# ADC_Board_Two_Board.net
KiCad netlist of a schematic drawn in EAGLE
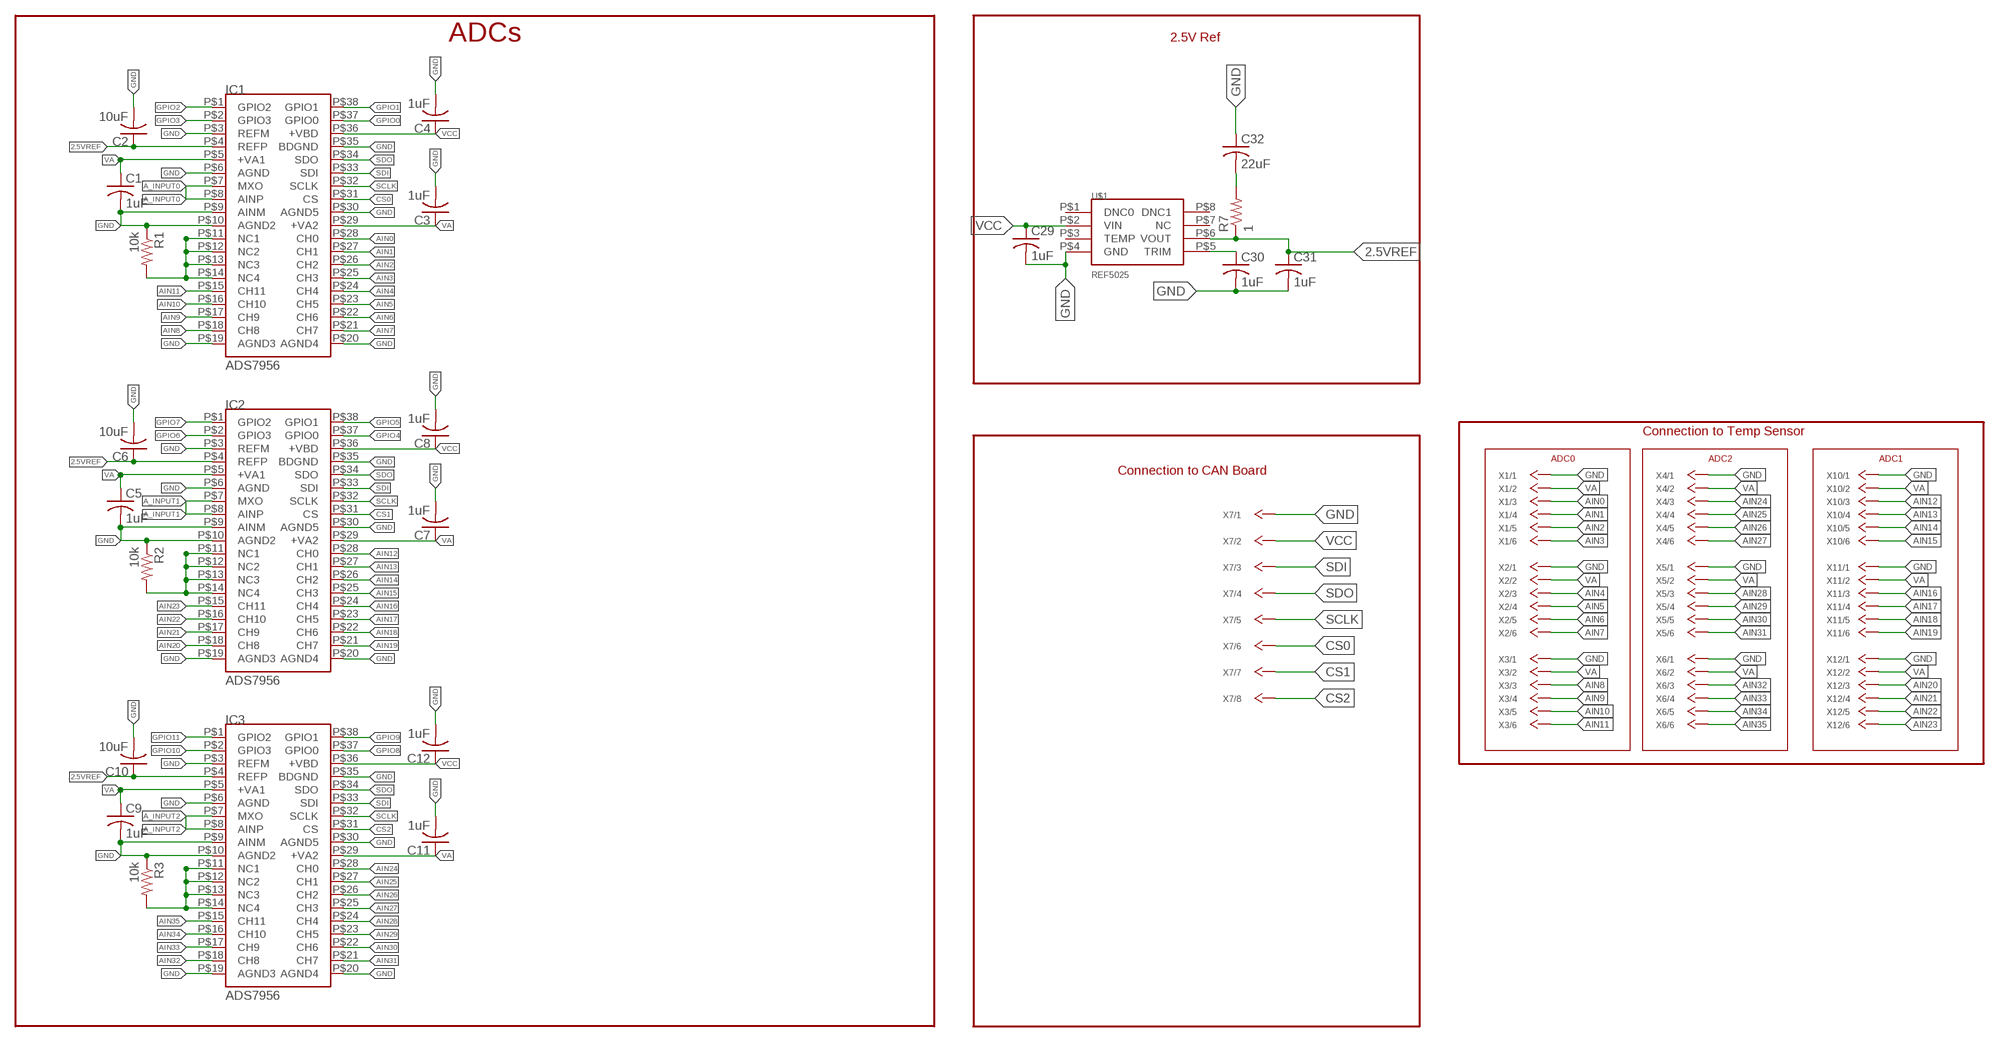
[diagram p0: schematic, sheet 1]

(export (version "E")
  (design (tool "Eeschema 10.0.6"))
  (components
    (comp (ref "C1")
      (value "1uF")
      (footprint "eagle-import:C0603")
      (libsource (lib "eagle-import") (part "C-USC0603"))
    )
    (comp (ref "C2")
      (value "10uF")
      (footprint "eagle-import:C0603")
      (libsource (lib "eagle-import") (part "C-USC0603"))
    )
    (comp (ref "C3")
      (value "1uF")
      (footprint "eagle-import:C0603")
      (libsource (lib "eagle-import") (part "C-USC0603"))
    )
    (comp (ref "C4")
      (value "1uF")
      (footprint "eagle-import:C0603")
      (libsource (lib "eagle-import") (part "C-USC0603"))
    )
    (comp (ref "C5")
      (value "1uF")
      (footprint "eagle-import:C0603")
      (libsource (lib "eagle-import") (part "C-USC0603"))
    )
    (comp (ref "C6")
      (value "10uF")
      (footprint "eagle-import:C0603")
      (libsource (lib "eagle-import") (part "C-USC0603"))
    )
    (comp (ref "C7")
      (value "1uF")
      (footprint "eagle-import:C0603")
      (libsource (lib "eagle-import") (part "C-USC0603"))
    )
    (comp (ref "C8")
      (value "1uF")
      (footprint "eagle-import:C0603")
      (libsource (lib "eagle-import") (part "C-USC0603"))
    )
    (comp (ref "C9")
      (value "1uF")
      (footprint "eagle-import:C0603")
      (libsource (lib "eagle-import") (part "C-USC0603"))
    )
    (comp (ref "C10")
      (value "10uF")
      (footprint "eagle-import:C0603")
      (libsource (lib "eagle-import") (part "C-USC0603"))
    )
    (comp (ref "C11")
      (value "1uF")
      (footprint "eagle-import:C0603")
      (libsource (lib "eagle-import") (part "C-USC0603"))
    )
    (comp (ref "C12")
      (value "1uF")
      (footprint "eagle-import:C0603")
      (libsource (lib "eagle-import") (part "C-USC0603"))
    )
    (comp (ref "C29")
      (value "1uF")
      (footprint "eagle-import:C0603")
      (libsource (lib "eagle-import") (part "C-USC0603"))
    )
    (comp (ref "C30")
      (value "1uF")
      (footprint "eagle-import:C0603")
      (libsource (lib "eagle-import") (part "C-USC0603"))
    )
    (comp (ref "C31")
      (value "1uF")
      (footprint "eagle-import:C0603")
      (libsource (lib "eagle-import") (part "C-USC0603"))
    )
    (comp (ref "C32")
      (value "22uF")
      (footprint "eagle-import:C0603")
      (libsource (lib "eagle-import") (part "C-USC0603"))
    )
    (comp (ref "IC1")
      (value "ADS7956")
      (footprint "eagle-import:TSSOP-38")
      (libsource (lib "eagle-import") (part "ADS7956"))
    )
    (comp (ref "IC2")
      (value "ADS7956")
      (footprint "eagle-import:TSSOP-38")
      (libsource (lib "eagle-import") (part "ADS7956"))
    )
    (comp (ref "IC3")
      (value "ADS7956")
      (footprint "eagle-import:TSSOP-38")
      (libsource (lib "eagle-import") (part "ADS7956"))
    )
    (comp (ref "R1")
      (value "10k")
      (footprint "eagle-import:R0603")
      (libsource (lib "eagle-import") (part "resistor_R-US_R0603"))
    )
    (comp (ref "R2")
      (value "10k")
      (footprint "eagle-import:R0603")
      (libsource (lib "eagle-import") (part "resistor_R-US_R0603"))
    )
    (comp (ref "R3")
      (value "10k")
      (footprint "eagle-import:R0603")
      (libsource (lib "eagle-import") (part "resistor_R-US_R0603"))
    )
    (comp (ref "R7")
      (value "1")
      (footprint "eagle-import:M0805")
      (libsource (lib "eagle-import") (part "R-US_M0805"))
    )
    (comp (ref "U$1")
      (value "REF5025")
      (footprint "eagle-import:TSSOP-8(TI)")
      (libsource (lib "eagle-import") (part "REF5025"))
    )
    (comp (ref "X1")
      (value "6_PIN_CONNTE_IDC")
      (footprint "eagle-import:2178710_IDC")
      (libsource (lib "eagle-import") (part "6_PIN_CONNTE_IDC"))
    )
    (comp (ref "X2")
      (value "6_PIN_CONNTE_IDC")
      (footprint "eagle-import:2178710_IDC")
      (libsource (lib "eagle-import") (part "6_PIN_CONNTE_IDC"))
    )
    (comp (ref "X3")
      (value "6_PIN_CONNTE_IDC")
      (footprint "eagle-import:2178710_IDC")
      (libsource (lib "eagle-import") (part "6_PIN_CONNTE_IDC"))
    )
    (comp (ref "X4")
      (value "6_PIN_CONNTE_IDC")
      (footprint "eagle-import:2178710_IDC")
      (libsource (lib "eagle-import") (part "6_PIN_CONNTE_IDC"))
    )
    (comp (ref "X5")
      (value "6_PIN_CONNTE_IDC")
      (footprint "eagle-import:2178710_IDC")
      (libsource (lib "eagle-import") (part "6_PIN_CONNTE_IDC"))
    )
    (comp (ref "X6")
      (value "6_PIN_CONNTE_IDC")
      (footprint "eagle-import:2178710_IDC")
      (libsource (lib "eagle-import") (part "6_PIN_CONNTE_IDC"))
    )
    (comp (ref "X7")
      (value "8_PIN_CONN")
      (footprint "eagle-import:8_PIN_MOLEX")
      (libsource (lib "eagle-import") (part "8_PIN_CONN"))
    )
    (comp (ref "X10")
      (value "6_PIN_CONNTE_IDC")
      (footprint "eagle-import:2178710_IDC")
      (libsource (lib "eagle-import") (part "6_PIN_CONNTE_IDC"))
    )
    (comp (ref "X11")
      (value "6_PIN_CONNTE_IDC")
      (footprint "eagle-import:2178710_IDC")
      (libsource (lib "eagle-import") (part "6_PIN_CONNTE_IDC"))
    )
    (comp (ref "X12")
      (value "6_PIN_CONNTE_IDC")
      (footprint "eagle-import:2178710_IDC")
      (libsource (lib "eagle-import") (part "6_PIN_CONNTE_IDC"))
    )
  )
  (nets
    (net (code "1") (name "2.5VREF") (class "Default")
      (node (ref "C10") (pin "1") (pinfunction "1_1") (pintype "passive"))
      (node (ref "C2") (pin "1") (pinfunction "1_1") (pintype "passive"))
      (node (ref "C31") (pin "1") (pinfunction "1_1") (pintype "passive"))
      (node (ref "C6") (pin "1") (pinfunction "1_1") (pintype "passive"))
      (node (ref "IC1") (pin "P$4") (pinfunction "REFP_P$4") (pintype "bidirectional"))
      (node (ref "IC2") (pin "P$4") (pinfunction "REFP_P$4") (pintype "bidirectional"))
      (node (ref "IC3") (pin "P$4") (pinfunction "REFP_P$4") (pintype "bidirectional"))
      (node (ref "R7") (pin "1") (pinfunction "1_1") (pintype "passive"))
      (node (ref "U$1") (pin "P$6") (pinfunction "VOUT_P$6") (pintype "bidirectional"))
    )
    (net (code "2") (name "AIN0") (class "Default")
      (node (ref "IC1") (pin "P$28") (pinfunction "CH0_P$28") (pintype "bidirectional"))
      (node (ref "X1") (pin "P$3") (pinfunction "$/1_P$3") (pintype "bidirectional"))
    )
    (net (code "3") (name "AIN1") (class "Default")
      (node (ref "IC1") (pin "P$27") (pinfunction "CH1_P$27") (pintype "bidirectional"))
      (node (ref "X1") (pin "P$4") (pinfunction "$/1_P$4") (pintype "bidirectional"))
    )
    (net (code "4") (name "AIN2") (class "Default")
      (node (ref "IC1") (pin "P$26") (pinfunction "CH2_P$26") (pintype "bidirectional"))
      (node (ref "X1") (pin "P$5") (pinfunction "$/1_P$5") (pintype "bidirectional"))
    )
    (net (code "5") (name "AIN3") (class "Default")
      (node (ref "IC1") (pin "P$25") (pinfunction "CH3_P$25") (pintype "bidirectional"))
      (node (ref "X1") (pin "P$6") (pinfunction "$/1_P$6") (pintype "bidirectional"))
    )
    (net (code "6") (name "AIN4") (class "Default")
      (node (ref "IC1") (pin "P$24") (pinfunction "CH4_P$24") (pintype "bidirectional"))
      (node (ref "X2") (pin "P$3") (pinfunction "$/1_P$3") (pintype "bidirectional"))
    )
    (net (code "7") (name "AIN5") (class "Default")
      (node (ref "IC1") (pin "P$23") (pinfunction "CH5_P$23") (pintype "bidirectional"))
      (node (ref "X2") (pin "P$4") (pinfunction "$/1_P$4") (pintype "bidirectional"))
    )
    (net (code "8") (name "AIN6") (class "Default")
      (node (ref "IC1") (pin "P$22") (pinfunction "CH6_P$22") (pintype "bidirectional"))
      (node (ref "X2") (pin "P$5") (pinfunction "$/1_P$5") (pintype "bidirectional"))
    )
    (net (code "9") (name "AIN7") (class "Default")
      (node (ref "IC1") (pin "P$21") (pinfunction "CH7_P$21") (pintype "bidirectional"))
      (node (ref "X2") (pin "P$6") (pinfunction "$/1_P$6") (pintype "bidirectional"))
    )
    (net (code "10") (name "AIN8") (class "Default")
      (node (ref "IC1") (pin "P$18") (pinfunction "CH8_P$18") (pintype "bidirectional"))
      (node (ref "X3") (pin "P$3") (pinfunction "$/1_P$3") (pintype "bidirectional"))
    )
    (net (code "11") (name "AIN9") (class "Default")
      (node (ref "IC1") (pin "P$17") (pinfunction "CH9_P$17") (pintype "bidirectional"))
      (node (ref "X3") (pin "P$4") (pinfunction "$/1_P$4") (pintype "bidirectional"))
    )
    (net (code "12") (name "AIN10") (class "Default")
      (node (ref "IC1") (pin "P$16") (pinfunction "CH10_P$16") (pintype "bidirectional"))
      (node (ref "X3") (pin "P$5") (pinfunction "$/1_P$5") (pintype "bidirectional"))
    )
    (net (code "13") (name "AIN11") (class "Default")
      (node (ref "IC1") (pin "P$15") (pinfunction "CH11_P$15") (pintype "bidirectional"))
      (node (ref "X3") (pin "P$6") (pinfunction "$/1_P$6") (pintype "bidirectional"))
    )
    (net (code "14") (name "AIN12") (class "Default")
      (node (ref "IC2") (pin "P$28") (pinfunction "CH0_P$28") (pintype "bidirectional"))
      (node (ref "X10") (pin "P$3") (pinfunction "$/1_P$3") (pintype "bidirectional"))
    )
    (net (code "15") (name "AIN13") (class "Default")
      (node (ref "IC2") (pin "P$27") (pinfunction "CH1_P$27") (pintype "bidirectional"))
      (node (ref "X10") (pin "P$4") (pinfunction "$/1_P$4") (pintype "bidirectional"))
    )
    (net (code "16") (name "AIN14") (class "Default")
      (node (ref "IC2") (pin "P$26") (pinfunction "CH2_P$26") (pintype "bidirectional"))
      (node (ref "X10") (pin "P$5") (pinfunction "$/1_P$5") (pintype "bidirectional"))
    )
    (net (code "17") (name "AIN15") (class "Default")
      (node (ref "IC2") (pin "P$25") (pinfunction "CH3_P$25") (pintype "bidirectional"))
      (node (ref "X10") (pin "P$6") (pinfunction "$/1_P$6") (pintype "bidirectional"))
    )
    (net (code "18") (name "AIN16") (class "Default")
      (node (ref "IC2") (pin "P$24") (pinfunction "CH4_P$24") (pintype "bidirectional"))
      (node (ref "X11") (pin "P$3") (pinfunction "$/1_P$3") (pintype "bidirectional"))
    )
    (net (code "19") (name "AIN17") (class "Default")
      (node (ref "IC2") (pin "P$23") (pinfunction "CH5_P$23") (pintype "bidirectional"))
      (node (ref "X11") (pin "P$4") (pinfunction "$/1_P$4") (pintype "bidirectional"))
    )
    (net (code "20") (name "AIN18") (class "Default")
      (node (ref "IC2") (pin "P$22") (pinfunction "CH6_P$22") (pintype "bidirectional"))
      (node (ref "X11") (pin "P$5") (pinfunction "$/1_P$5") (pintype "bidirectional"))
    )
    (net (code "21") (name "AIN19") (class "Default")
      (node (ref "IC2") (pin "P$21") (pinfunction "CH7_P$21") (pintype "bidirectional"))
      (node (ref "X11") (pin "P$6") (pinfunction "$/1_P$6") (pintype "bidirectional"))
    )
    (net (code "22") (name "AIN20") (class "Default")
      (node (ref "IC2") (pin "P$18") (pinfunction "CH8_P$18") (pintype "bidirectional"))
      (node (ref "X12") (pin "P$3") (pinfunction "$/1_P$3") (pintype "bidirectional"))
    )
    (net (code "23") (name "AIN21") (class "Default")
      (node (ref "IC2") (pin "P$17") (pinfunction "CH9_P$17") (pintype "bidirectional"))
      (node (ref "X12") (pin "P$4") (pinfunction "$/1_P$4") (pintype "bidirectional"))
    )
    (net (code "24") (name "AIN22") (class "Default")
      (node (ref "IC2") (pin "P$16") (pinfunction "CH10_P$16") (pintype "bidirectional"))
      (node (ref "X12") (pin "P$5") (pinfunction "$/1_P$5") (pintype "bidirectional"))
    )
    (net (code "25") (name "AIN23") (class "Default")
      (node (ref "IC2") (pin "P$15") (pinfunction "CH11_P$15") (pintype "bidirectional"))
      (node (ref "X12") (pin "P$6") (pinfunction "$/1_P$6") (pintype "bidirectional"))
    )
    (net (code "26") (name "AIN24") (class "Default")
      (node (ref "IC3") (pin "P$28") (pinfunction "CH0_P$28") (pintype "bidirectional"))
      (node (ref "X4") (pin "P$3") (pinfunction "$/1_P$3") (pintype "bidirectional"))
    )
    (net (code "27") (name "AIN25") (class "Default")
      (node (ref "IC3") (pin "P$27") (pinfunction "CH1_P$27") (pintype "bidirectional"))
      (node (ref "X4") (pin "P$4") (pinfunction "$/1_P$4") (pintype "bidirectional"))
    )
    (net (code "28") (name "AIN26") (class "Default")
      (node (ref "IC3") (pin "P$26") (pinfunction "CH2_P$26") (pintype "bidirectional"))
      (node (ref "X4") (pin "P$5") (pinfunction "$/1_P$5") (pintype "bidirectional"))
    )
    (net (code "29") (name "AIN27") (class "Default")
      (node (ref "IC3") (pin "P$25") (pinfunction "CH3_P$25") (pintype "bidirectional"))
      (node (ref "X4") (pin "P$6") (pinfunction "$/1_P$6") (pintype "bidirectional"))
    )
    (net (code "30") (name "AIN28") (class "Default")
      (node (ref "IC3") (pin "P$24") (pinfunction "CH4_P$24") (pintype "bidirectional"))
      (node (ref "X5") (pin "P$3") (pinfunction "$/1_P$3") (pintype "bidirectional"))
    )
    (net (code "31") (name "AIN29") (class "Default")
      (node (ref "IC3") (pin "P$23") (pinfunction "CH5_P$23") (pintype "bidirectional"))
      (node (ref "X5") (pin "P$4") (pinfunction "$/1_P$4") (pintype "bidirectional"))
    )
    (net (code "32") (name "AIN30") (class "Default")
      (node (ref "IC3") (pin "P$22") (pinfunction "CH6_P$22") (pintype "bidirectional"))
      (node (ref "X5") (pin "P$5") (pinfunction "$/1_P$5") (pintype "bidirectional"))
    )
    (net (code "33") (name "AIN31") (class "Default")
      (node (ref "IC3") (pin "P$21") (pinfunction "CH7_P$21") (pintype "bidirectional"))
      (node (ref "X5") (pin "P$6") (pinfunction "$/1_P$6") (pintype "bidirectional"))
    )
    (net (code "34") (name "AIN32") (class "Default")
      (node (ref "IC3") (pin "P$18") (pinfunction "CH8_P$18") (pintype "bidirectional"))
      (node (ref "X6") (pin "P$3") (pinfunction "$/1_P$3") (pintype "bidirectional"))
    )
    (net (code "35") (name "AIN33") (class "Default")
      (node (ref "IC3") (pin "P$17") (pinfunction "CH9_P$17") (pintype "bidirectional"))
      (node (ref "X6") (pin "P$4") (pinfunction "$/1_P$4") (pintype "bidirectional"))
    )
    (net (code "36") (name "AIN34") (class "Default")
      (node (ref "IC3") (pin "P$16") (pinfunction "CH10_P$16") (pintype "bidirectional"))
      (node (ref "X6") (pin "P$5") (pinfunction "$/1_P$5") (pintype "bidirectional"))
    )
    (net (code "37") (name "AIN35") (class "Default")
      (node (ref "IC3") (pin "P$15") (pinfunction "CH11_P$15") (pintype "bidirectional"))
      (node (ref "X6") (pin "P$6") (pinfunction "$/1_P$6") (pintype "bidirectional"))
    )
    (net (code "38") (name "A_INPUT0") (class "Default")
      (node (ref "IC1") (pin "P$7") (pinfunction "MXO_P$7") (pintype "bidirectional"))
      (node (ref "IC1") (pin "P$8") (pinfunction "AINP_P$8") (pintype "bidirectional"))
    )
    (net (code "39") (name "A_INPUT1") (class "Default")
      (node (ref "IC2") (pin "P$7") (pinfunction "MXO_P$7") (pintype "bidirectional"))
      (node (ref "IC2") (pin "P$8") (pinfunction "AINP_P$8") (pintype "bidirectional"))
    )
    (net (code "40") (name "A_INPUT2") (class "Default")
      (node (ref "IC3") (pin "P$7") (pinfunction "MXO_P$7") (pintype "bidirectional"))
      (node (ref "IC3") (pin "P$8") (pinfunction "AINP_P$8") (pintype "bidirectional"))
    )
    (net (code "41") (name "CS0") (class "Default")
      (node (ref "IC1") (pin "P$31") (pinfunction "CS_P$31") (pintype "bidirectional"))
      (node (ref "X7") (pin "P$6") (pinfunction "$/1_P$6") (pintype "bidirectional"))
    )
    (net (code "42") (name "CS1") (class "Default")
      (node (ref "IC2") (pin "P$31") (pinfunction "CS_P$31") (pintype "bidirectional"))
      (node (ref "X7") (pin "P$7") (pinfunction "$/1_P$7") (pintype "bidirectional"))
    )
    (net (code "43") (name "CS2") (class "Default")
      (node (ref "IC3") (pin "P$31") (pinfunction "CS_P$31") (pintype "bidirectional"))
      (node (ref "X7") (pin "P$8") (pinfunction "$/1_P$8") (pintype "bidirectional"))
    )
    (net (code "44") (name "GND") (class "Default")
      (node (ref "C1") (pin "2") (pinfunction "2_2") (pintype "passive"))
      (node (ref "C10") (pin "2") (pinfunction "2_2") (pintype "passive"))
      (node (ref "C11") (pin "2") (pinfunction "2_2") (pintype "passive"))
      (node (ref "C12") (pin "2") (pinfunction "2_2") (pintype "passive"))
      (node (ref "C2") (pin "2") (pinfunction "2_2") (pintype "passive"))
      (node (ref "C29") (pin "2") (pinfunction "2_2") (pintype "passive"))
      (node (ref "C3") (pin "2") (pinfunction "2_2") (pintype "passive"))
      (node (ref "C30") (pin "2") (pinfunction "2_2") (pintype "passive"))
      (node (ref "C31") (pin "2") (pinfunction "2_2") (pintype "passive"))
      (node (ref "C32") (pin "1") (pinfunction "1_1") (pintype "passive"))
      (node (ref "C4") (pin "2") (pinfunction "2_2") (pintype "passive"))
      (node (ref "C5") (pin "2") (pinfunction "2_2") (pintype "passive"))
      (node (ref "C6") (pin "2") (pinfunction "2_2") (pintype "passive"))
      (node (ref "C7") (pin "2") (pinfunction "2_2") (pintype "passive"))
      (node (ref "C8") (pin "2") (pinfunction "2_2") (pintype "passive"))
      (node (ref "C9") (pin "2") (pinfunction "2_2") (pintype "passive"))
      (node (ref "IC1") (pin "P$10") (pinfunction "AGND2_P$10") (pintype "bidirectional"))
      (node (ref "IC1") (pin "P$19") (pinfunction "AGND3_P$19") (pintype "bidirectional"))
      (node (ref "IC1") (pin "P$20") (pinfunction "AGND4_P$20") (pintype "bidirectional"))
      (node (ref "IC1") (pin "P$3") (pinfunction "REFM_P$3") (pintype "bidirectional"))
      (node (ref "IC1") (pin "P$30") (pinfunction "AGND5_P$30") (pintype "bidirectional"))
      (node (ref "IC1") (pin "P$35") (pinfunction "BDGND_P$35") (pintype "bidirectional"))
      (node (ref "IC1") (pin "P$6") (pinfunction "AGND_P$6") (pintype "bidirectional"))
      (node (ref "IC1") (pin "P$9") (pinfunction "AINM_P$9") (pintype "bidirectional"))
      (node (ref "IC2") (pin "P$10") (pinfunction "AGND2_P$10") (pintype "bidirectional"))
      (node (ref "IC2") (pin "P$19") (pinfunction "AGND3_P$19") (pintype "bidirectional"))
      (node (ref "IC2") (pin "P$20") (pinfunction "AGND4_P$20") (pintype "bidirectional"))
      (node (ref "IC2") (pin "P$3") (pinfunction "REFM_P$3") (pintype "bidirectional"))
      (node (ref "IC2") (pin "P$30") (pinfunction "AGND5_P$30") (pintype "bidirectional"))
      (node (ref "IC2") (pin "P$35") (pinfunction "BDGND_P$35") (pintype "bidirectional"))
      (node (ref "IC2") (pin "P$6") (pinfunction "AGND_P$6") (pintype "bidirectional"))
      (node (ref "IC2") (pin "P$9") (pinfunction "AINM_P$9") (pintype "bidirectional"))
      (node (ref "IC3") (pin "P$10") (pinfunction "AGND2_P$10") (pintype "bidirectional"))
      (node (ref "IC3") (pin "P$19") (pinfunction "AGND3_P$19") (pintype "bidirectional"))
      (node (ref "IC3") (pin "P$20") (pinfunction "AGND4_P$20") (pintype "bidirectional"))
      (node (ref "IC3") (pin "P$3") (pinfunction "REFM_P$3") (pintype "bidirectional"))
      (node (ref "IC3") (pin "P$30") (pinfunction "AGND5_P$30") (pintype "bidirectional"))
      (node (ref "IC3") (pin "P$35") (pinfunction "BDGND_P$35") (pintype "bidirectional"))
      (node (ref "IC3") (pin "P$6") (pinfunction "AGND_P$6") (pintype "bidirectional"))
      (node (ref "IC3") (pin "P$9") (pinfunction "AINM_P$9") (pintype "bidirectional"))
      (node (ref "R1") (pin "1") (pinfunction "1_1") (pintype "passive"))
      (node (ref "R2") (pin "1") (pinfunction "1_1") (pintype "passive"))
      (node (ref "R3") (pin "1") (pinfunction "1_1") (pintype "passive"))
      (node (ref "U$1") (pin "P$4") (pinfunction "GND_P$4") (pintype "bidirectional"))
      (node (ref "X1") (pin "P$1") (pinfunction "$/1_P$1") (pintype "bidirectional"))
      (node (ref "X10") (pin "P$1") (pinfunction "$/1_P$1") (pintype "bidirectional"))
      (node (ref "X11") (pin "P$1") (pinfunction "$/1_P$1") (pintype "bidirectional"))
      (node (ref "X12") (pin "P$1") (pinfunction "$/1_P$1") (pintype "bidirectional"))
      (node (ref "X2") (pin "P$1") (pinfunction "$/1_P$1") (pintype "bidirectional"))
      (node (ref "X3") (pin "P$1") (pinfunction "$/1_P$1") (pintype "bidirectional"))
      (node (ref "X4") (pin "P$1") (pinfunction "$/1_P$1") (pintype "bidirectional"))
      (node (ref "X5") (pin "P$1") (pinfunction "$/1_P$1") (pintype "bidirectional"))
      (node (ref "X6") (pin "P$1") (pinfunction "$/1_P$1") (pintype "bidirectional"))
      (node (ref "X7") (pin "P$1") (pinfunction "$/1_P$1") (pintype "bidirectional"))
    )
    (net (code "45") (name "GPIO0") (class "Default")
      (node (ref "IC1") (pin "P$37") (pinfunction "GPIO0_P$37") (pintype "bidirectional"))
    )
    (net (code "46") (name "GPIO1") (class "Default")
      (node (ref "IC1") (pin "P$38") (pinfunction "GPIO1_P$38") (pintype "bidirectional"))
    )
    (net (code "47") (name "GPIO2") (class "Default")
      (node (ref "IC1") (pin "P$1") (pinfunction "GPIO2_P$1") (pintype "bidirectional"))
    )
    (net (code "48") (name "GPIO3") (class "Default")
      (node (ref "IC1") (pin "P$2") (pinfunction "GPIO3_P$2") (pintype "bidirectional"))
    )
    (net (code "49") (name "GPIO4") (class "Default")
      (node (ref "IC2") (pin "P$37") (pinfunction "GPIO0_P$37") (pintype "bidirectional"))
    )
    (net (code "50") (name "GPIO5") (class "Default")
      (node (ref "IC2") (pin "P$38") (pinfunction "GPIO1_P$38") (pintype "bidirectional"))
    )
    (net (code "51") (name "GPIO6") (class "Default")
      (node (ref "IC2") (pin "P$2") (pinfunction "GPIO3_P$2") (pintype "bidirectional"))
    )
    (net (code "52") (name "GPIO7") (class "Default")
      (node (ref "IC2") (pin "P$1") (pinfunction "GPIO2_P$1") (pintype "bidirectional"))
    )
    (net (code "53") (name "GPIO8") (class "Default")
      (node (ref "IC3") (pin "P$37") (pinfunction "GPIO0_P$37") (pintype "bidirectional"))
    )
    (net (code "54") (name "GPIO9") (class "Default")
      (node (ref "IC3") (pin "P$38") (pinfunction "GPIO1_P$38") (pintype "bidirectional"))
    )
    (net (code "55") (name "GPIO10") (class "Default")
      (node (ref "IC3") (pin "P$2") (pinfunction "GPIO3_P$2") (pintype "bidirectional"))
    )
    (net (code "56") (name "GPIO11") (class "Default")
      (node (ref "IC3") (pin "P$1") (pinfunction "GPIO2_P$1") (pintype "bidirectional"))
    )
    (net (code "57") (name "Net-(C32-Pad2)") (class "Default")
      (node (ref "C32") (pin "2") (pinfunction "2_2") (pintype "passive"))
      (node (ref "R7") (pin "2") (pinfunction "2_2") (pintype "passive"))
    )
    (net (code "58") (name "Net-(IC1-NC1)") (class "Default")
      (node (ref "IC1") (pin "P$11") (pinfunction "NC1_P$11") (pintype "bidirectional"))
      (node (ref "IC1") (pin "P$12") (pinfunction "NC2_P$12") (pintype "bidirectional"))
      (node (ref "IC1") (pin "P$13") (pinfunction "NC3_P$13") (pintype "bidirectional"))
      (node (ref "IC1") (pin "P$14") (pinfunction "NC4_P$14") (pintype "bidirectional"))
      (node (ref "R1") (pin "2") (pinfunction "2_2") (pintype "passive"))
    )
    (net (code "59") (name "Net-(IC2-NC1)") (class "Default")
      (node (ref "IC2") (pin "P$11") (pinfunction "NC1_P$11") (pintype "bidirectional"))
      (node (ref "IC2") (pin "P$12") (pinfunction "NC2_P$12") (pintype "bidirectional"))
      (node (ref "IC2") (pin "P$13") (pinfunction "NC3_P$13") (pintype "bidirectional"))
      (node (ref "IC2") (pin "P$14") (pinfunction "NC4_P$14") (pintype "bidirectional"))
      (node (ref "R2") (pin "2") (pinfunction "2_2") (pintype "passive"))
    )
    (net (code "60") (name "Net-(IC3-NC1)") (class "Default")
      (node (ref "IC3") (pin "P$11") (pinfunction "NC1_P$11") (pintype "bidirectional"))
      (node (ref "IC3") (pin "P$12") (pinfunction "NC2_P$12") (pintype "bidirectional"))
      (node (ref "IC3") (pin "P$13") (pinfunction "NC3_P$13") (pintype "bidirectional"))
      (node (ref "IC3") (pin "P$14") (pinfunction "NC4_P$14") (pintype "bidirectional"))
      (node (ref "R3") (pin "2") (pinfunction "2_2") (pintype "passive"))
    )
    (net (code "61") (name "Net-(U$1-TRIM)") (class "Default")
      (node (ref "C30") (pin "1") (pinfunction "1_1") (pintype "passive"))
      (node (ref "U$1") (pin "P$5") (pinfunction "TRIM_P$5") (pintype "bidirectional"))
    )
    (net (code "62") (name "SCLK") (class "Default")
      (node (ref "IC1") (pin "P$32") (pinfunction "SCLK_P$32") (pintype "bidirectional"))
      (node (ref "IC2") (pin "P$32") (pinfunction "SCLK_P$32") (pintype "bidirectional"))
      (node (ref "IC3") (pin "P$32") (pinfunction "SCLK_P$32") (pintype "bidirectional"))
      (node (ref "X7") (pin "P$5") (pinfunction "$/1_P$5") (pintype "bidirectional"))
    )
    (net (code "63") (name "SDI") (class "Default")
      (node (ref "IC1") (pin "P$33") (pinfunction "SDI_P$33") (pintype "bidirectional"))
      (node (ref "IC2") (pin "P$33") (pinfunction "SDI_P$33") (pintype "bidirectional"))
      (node (ref "IC3") (pin "P$33") (pinfunction "SDI_P$33") (pintype "bidirectional"))
      (node (ref "X7") (pin "P$3") (pinfunction "$/1_P$3") (pintype "bidirectional"))
    )
    (net (code "64") (name "SDO") (class "Default")
      (node (ref "IC1") (pin "P$34") (pinfunction "SDO_P$34") (pintype "bidirectional"))
      (node (ref "IC2") (pin "P$34") (pinfunction "SDO_P$34") (pintype "bidirectional"))
      (node (ref "IC3") (pin "P$34") (pinfunction "SDO_P$34") (pintype "bidirectional"))
      (node (ref "X7") (pin "P$4") (pinfunction "$/1_P$4") (pintype "bidirectional"))
    )
    (net (code "65") (name "VA") (class "Default")
      (node (ref "C1") (pin "1") (pinfunction "1_1") (pintype "passive"))
      (node (ref "C11") (pin "1") (pinfunction "1_1") (pintype "passive"))
      (node (ref "C3") (pin "1") (pinfunction "1_1") (pintype "passive"))
      (node (ref "C5") (pin "1") (pinfunction "1_1") (pintype "passive"))
      (node (ref "C7") (pin "1") (pinfunction "1_1") (pintype "passive"))
      (node (ref "C9") (pin "1") (pinfunction "1_1") (pintype "passive"))
      (node (ref "IC1") (pin "P$29") (pinfunction "+VA2_P$29") (pintype "bidirectional"))
      (node (ref "IC1") (pin "P$5") (pinfunction "+VA1_P$5") (pintype "bidirectional"))
      (node (ref "IC2") (pin "P$29") (pinfunction "+VA2_P$29") (pintype "bidirectional"))
      (node (ref "IC2") (pin "P$5") (pinfunction "+VA1_P$5") (pintype "bidirectional"))
      (node (ref "IC3") (pin "P$29") (pinfunction "+VA2_P$29") (pintype "bidirectional"))
      (node (ref "IC3") (pin "P$5") (pinfunction "+VA1_P$5") (pintype "bidirectional"))
      (node (ref "X1") (pin "P$2") (pinfunction "$/1_P$2") (pintype "bidirectional"))
      (node (ref "X10") (pin "P$2") (pinfunction "$/1_P$2") (pintype "bidirectional"))
      (node (ref "X11") (pin "P$2") (pinfunction "$/1_P$2") (pintype "bidirectional"))
      (node (ref "X12") (pin "P$2") (pinfunction "$/1_P$2") (pintype "bidirectional"))
      (node (ref "X2") (pin "P$2") (pinfunction "$/1_P$2") (pintype "bidirectional"))
      (node (ref "X3") (pin "P$2") (pinfunction "$/1_P$2") (pintype "bidirectional"))
      (node (ref "X4") (pin "P$2") (pinfunction "$/1_P$2") (pintype "bidirectional"))
      (node (ref "X5") (pin "P$2") (pinfunction "$/1_P$2") (pintype "bidirectional"))
      (node (ref "X6") (pin "P$2") (pinfunction "$/1_P$2") (pintype "bidirectional"))
    )
    (net (code "66") (name "VCC") (class "Default")
      (node (ref "C12") (pin "1") (pinfunction "1_1") (pintype "passive"))
      (node (ref "C29") (pin "1") (pinfunction "1_1") (pintype "passive"))
      (node (ref "C4") (pin "1") (pinfunction "1_1") (pintype "passive"))
      (node (ref "C8") (pin "1") (pinfunction "1_1") (pintype "passive"))
      (node (ref "IC1") (pin "P$36") (pinfunction "+VBD_P$36") (pintype "bidirectional"))
      (node (ref "IC2") (pin "P$36") (pinfunction "+VBD_P$36") (pintype "bidirectional"))
      (node (ref "IC3") (pin "P$36") (pinfunction "+VBD_P$36") (pintype "bidirectional"))
      (node (ref "U$1") (pin "P$2") (pinfunction "VIN_P$2") (pintype "bidirectional"))
      (node (ref "X7") (pin "P$2") (pinfunction "$/1_P$2") (pintype "bidirectional"))
    )
    (net (code "67") (name "unconnected-(U$1-DNC0-PadP$1)") (class "Default")
      (node (ref "U$1") (pin "P$1") (pinfunction "DNC0_P$1") (pintype "bidirectional"))
    )
    (net (code "68") (name "unconnected-(U$1-DNC1-PadP$8)") (class "Default")
      (node (ref "U$1") (pin "P$8") (pinfunction "DNC1_P$8") (pintype "bidirectional"))
    )
    (net (code "69") (name "unconnected-(U$1-NC-PadP$7)") (class "Default")
      (node (ref "U$1") (pin "P$7") (pinfunction "NC_P$7") (pintype "bidirectional"))
    )
    (net (code "70") (name "unconnected-(U$1-TEMP-PadP$3)") (class "Default")
      (node (ref "U$1") (pin "P$3") (pinfunction "TEMP_P$3") (pintype "bidirectional"))
    )
  )
)
